# LCD_Connectors.net
KiCad netlist of a schematic drawn in Altium Designer
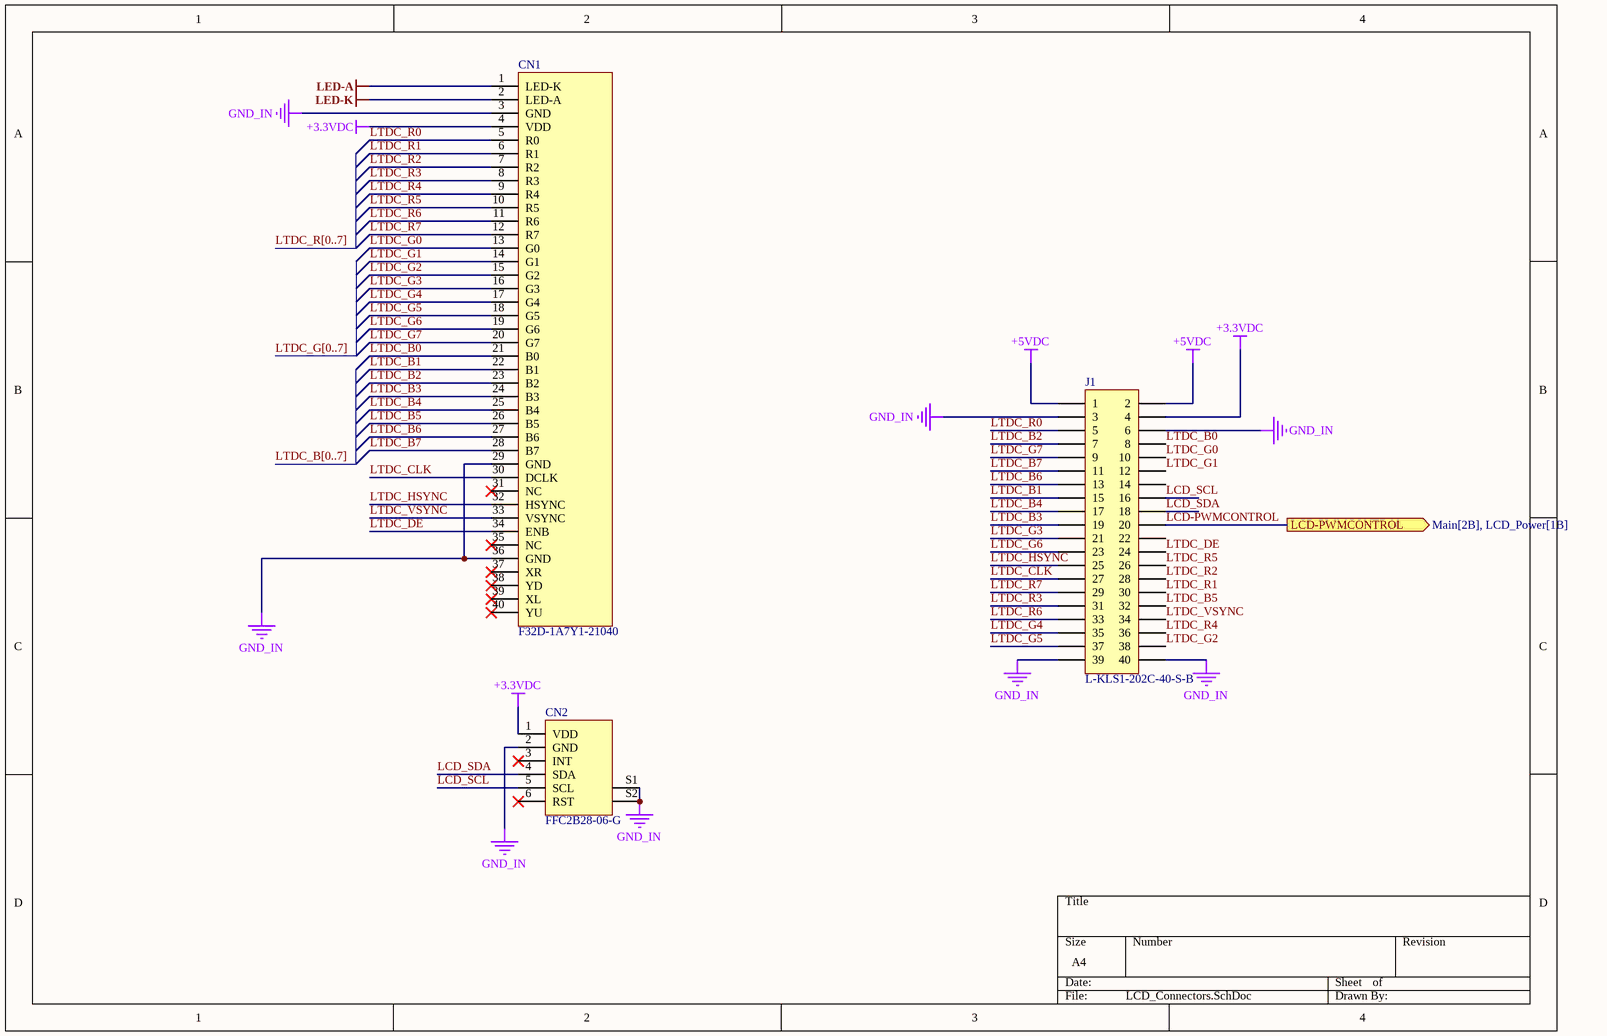
[diagram p0: LCD_Connectors.SchDoc]

(export (version "E")
  (design (tool "Eeschema 10.0.6"))
  (components
    (comp (ref "CN1")
      (value "F32D-1A7Y1-21040")
      (footprint "FPC_40POS_DOUBLESIDE")
      (description "CONN FFC BOTTOM 40POS 0.5MM R/A")
      (libsource (lib "IM_v1.0") (part "FPC CONN 40POS"))
    )
    (comp (ref "CN2")
      (value "FFC2B28-06-G")
      (footprint "FPC_6POS_DOUBLESIDE")
      (libsource (lib "IM_v1.0") (part "FPC CONN 6POS"))
    )
    (comp (ref "J1")
      (value "L-KLS1-202C-40-S-B")
      (footprint "L-KLS1-202C-40-T-B")
      (description "BOX HEADER 40PIN(2x20) 1.27MM THT V/T MALE BLACK")
      (libsource (lib "IM_v1.0") (part "2X20"))
    )
  )
  (nets
    (net (code "1") (name "+3.3VDC") (class "Default")
      (node (ref "CN1") (pin "4") (pinfunction "VDD_4") (pintype "passive"))
      (node (ref "CN2") (pin "1") (pinfunction "VDD_1") (pintype "passive"))
      (node (ref "J1") (pin "4") (pinfunction "4_4") (pintype "passive"))
    )
    (net (code "2") (name "+5VDC") (class "Default")
      (node (ref "J1") (pin "1") (pinfunction "1_1") (pintype "passive"))
      (node (ref "J1") (pin "2") (pinfunction "2_2") (pintype "passive"))
    )
    (net (code "3") (name "/LCD-PWMCONTROL") (class "Default")
      (node (ref "J1") (pin "20") (pinfunction "20_20") (pintype "passive"))
    )
    (net (code "4") (name "/LCD_SCL") (class "Default")
      (node (ref "CN2") (pin "5") (pinfunction "SCL_5") (pintype "passive"))
      (node (ref "J1") (pin "16") (pinfunction "16_16") (pintype "passive"))
    )
    (net (code "5") (name "/LCD_SDA") (class "Default")
      (node (ref "CN2") (pin "4") (pinfunction "SDA_4") (pintype "passive"))
      (node (ref "J1") (pin "18") (pinfunction "18_18") (pintype "passive"))
    )
    (net (code "6") (name "/LTDC_B0") (class "Default")
      (node (ref "CN1") (pin "21") (pinfunction "B0_21") (pintype "passive"))
      (node (ref "J1") (pin "8") (pinfunction "8_8") (pintype "passive"))
    )
    (net (code "7") (name "/LTDC_B1") (class "Default")
      (node (ref "CN1") (pin "22") (pinfunction "B1_22") (pintype "passive"))
      (node (ref "J1") (pin "15") (pinfunction "15_15") (pintype "passive"))
    )
    (net (code "8") (name "/LTDC_B2") (class "Default")
      (node (ref "CN1") (pin "23") (pinfunction "B2_23") (pintype "passive"))
      (node (ref "J1") (pin "7") (pinfunction "7_7") (pintype "passive"))
    )
    (net (code "9") (name "/LTDC_B3") (class "Default")
      (node (ref "CN1") (pin "24") (pinfunction "B3_24") (pintype "passive"))
      (node (ref "J1") (pin "19") (pinfunction "19_19") (pintype "passive"))
    )
    (net (code "10") (name "/LTDC_B4") (class "Default")
      (node (ref "CN1") (pin "25") (pinfunction "B4_25") (pintype "passive"))
      (node (ref "J1") (pin "17") (pinfunction "17_17") (pintype "passive"))
    )
    (net (code "11") (name "/LTDC_B5") (class "Default")
      (node (ref "CN1") (pin "26") (pinfunction "B5_26") (pintype "passive"))
      (node (ref "J1") (pin "32") (pinfunction "32_32") (pintype "passive"))
    )
    (net (code "12") (name "/LTDC_B6") (class "Default")
      (node (ref "CN1") (pin "27") (pinfunction "B6_27") (pintype "passive"))
      (node (ref "J1") (pin "13") (pinfunction "13_13") (pintype "passive"))
    )
    (net (code "13") (name "/LTDC_B7") (class "Default")
      (node (ref "CN1") (pin "28") (pinfunction "B7_28") (pintype "passive"))
      (node (ref "J1") (pin "11") (pinfunction "11_11") (pintype "passive"))
    )
    (net (code "15") (name "/LTDC_CLK") (class "Default")
      (node (ref "CN1") (pin "30") (pinfunction "DCLK_30") (pintype "passive"))
      (node (ref "J1") (pin "27") (pinfunction "27_27") (pintype "passive"))
    )
    (net (code "16") (name "/LTDC_DE") (class "Default")
      (node (ref "CN1") (pin "34") (pinfunction "ENB_34") (pintype "passive"))
      (node (ref "J1") (pin "24") (pinfunction "24_24") (pintype "passive"))
    )
    (net (code "17") (name "/LTDC_G0") (class "Default")
      (node (ref "CN1") (pin "13") (pinfunction "G0_13") (pintype "passive"))
      (node (ref "J1") (pin "10") (pinfunction "10_10") (pintype "passive"))
    )
    (net (code "18") (name "/LTDC_G1") (class "Default")
      (node (ref "CN1") (pin "14") (pinfunction "G1_14") (pintype "passive"))
      (node (ref "J1") (pin "12") (pinfunction "12_12") (pintype "passive"))
    )
    (net (code "19") (name "/LTDC_G2") (class "Default")
      (node (ref "CN1") (pin "15") (pinfunction "G2_15") (pintype "passive"))
      (node (ref "J1") (pin "38") (pinfunction "38_38") (pintype "passive"))
    )
    (net (code "20") (name "/LTDC_G3") (class "Default")
      (node (ref "CN1") (pin "16") (pinfunction "G3_16") (pintype "passive"))
      (node (ref "J1") (pin "21") (pinfunction "21_21") (pintype "passive"))
    )
    (net (code "21") (name "/LTDC_G4") (class "Default")
      (node (ref "CN1") (pin "17") (pinfunction "G4_17") (pintype "passive"))
      (node (ref "J1") (pin "35") (pinfunction "35_35") (pintype "passive"))
    )
    (net (code "22") (name "/LTDC_G5") (class "Default")
      (node (ref "CN1") (pin "18") (pinfunction "G5_18") (pintype "passive"))
      (node (ref "J1") (pin "37") (pinfunction "37_37") (pintype "passive"))
    )
    (net (code "23") (name "/LTDC_G6") (class "Default")
      (node (ref "CN1") (pin "19") (pinfunction "G6_19") (pintype "passive"))
      (node (ref "J1") (pin "23") (pinfunction "23_23") (pintype "passive"))
    )
    (net (code "24") (name "/LTDC_G7") (class "Default")
      (node (ref "CN1") (pin "20") (pinfunction "G7_20") (pintype "passive"))
      (node (ref "J1") (pin "9") (pinfunction "9_9") (pintype "passive"))
    )
    (net (code "26") (name "/LTDC_HSYNC") (class "Default")
      (node (ref "CN1") (pin "32") (pinfunction "HSYNC_32") (pintype "passive"))
      (node (ref "J1") (pin "25") (pinfunction "25_25") (pintype "passive"))
    )
    (net (code "27") (name "/LTDC_R0") (class "Default")
      (node (ref "CN1") (pin "5") (pinfunction "R0_5") (pintype "passive"))
      (node (ref "J1") (pin "5") (pinfunction "5_5") (pintype "passive"))
    )
    (net (code "28") (name "/LTDC_R1") (class "Default")
      (node (ref "CN1") (pin "6") (pinfunction "R1_6") (pintype "passive"))
      (node (ref "J1") (pin "30") (pinfunction "30_30") (pintype "passive"))
    )
    (net (code "29") (name "/LTDC_R2") (class "Default")
      (node (ref "CN1") (pin "7") (pinfunction "R2_7") (pintype "passive"))
      (node (ref "J1") (pin "28") (pinfunction "28_28") (pintype "passive"))
    )
    (net (code "30") (name "/LTDC_R3") (class "Default")
      (node (ref "CN1") (pin "8") (pinfunction "R3_8") (pintype "passive"))
      (node (ref "J1") (pin "31") (pinfunction "31_31") (pintype "passive"))
    )
    (net (code "31") (name "/LTDC_R4") (class "Default")
      (node (ref "CN1") (pin "9") (pinfunction "R4_9") (pintype "passive"))
      (node (ref "J1") (pin "36") (pinfunction "36_36") (pintype "passive"))
    )
    (net (code "32") (name "/LTDC_R5") (class "Default")
      (node (ref "CN1") (pin "10") (pinfunction "R5_10") (pintype "passive"))
      (node (ref "J1") (pin "26") (pinfunction "26_26") (pintype "passive"))
    )
    (net (code "33") (name "/LTDC_R6") (class "Default")
      (node (ref "CN1") (pin "11") (pinfunction "R6_11") (pintype "passive"))
      (node (ref "J1") (pin "33") (pinfunction "33_33") (pintype "passive"))
    )
    (net (code "34") (name "/LTDC_R7") (class "Default")
      (node (ref "CN1") (pin "12") (pinfunction "R7_12") (pintype "passive"))
      (node (ref "J1") (pin "29") (pinfunction "29_29") (pintype "passive"))
    )
    (net (code "36") (name "/LTDC_VSYNC") (class "Default")
      (node (ref "CN1") (pin "33") (pinfunction "VSYNC_33") (pintype "passive"))
      (node (ref "J1") (pin "34") (pinfunction "34_34") (pintype "passive"))
    )
    (net (code "37") (name "GND_IN") (class "Default")
      (node (ref "CN1") (pin "29") (pinfunction "GND_29") (pintype "passive"))
      (node (ref "CN1") (pin "3") (pinfunction "GND_3") (pintype "passive"))
      (node (ref "CN1") (pin "36") (pinfunction "GND_36") (pintype "passive"))
      (node (ref "CN2") (pin "2") (pinfunction "GND_2") (pintype "passive"))
      (node (ref "CN2") (pin "S1") (pinfunction "SHIELD_S1") (pintype "passive"))
      (node (ref "CN2") (pin "S2") (pinfunction "SHIELD_S2") (pintype "passive"))
      (node (ref "J1") (pin "3") (pinfunction "3_3") (pintype "passive"))
      (node (ref "J1") (pin "39") (pinfunction "39_39") (pintype "passive"))
      (node (ref "J1") (pin "40") (pinfunction "40_40") (pintype "passive"))
      (node (ref "J1") (pin "6") (pinfunction "6_6") (pintype "passive"))
    )
    (net (code "38") (name "LED-A") (class "Default")
      (node (ref "CN1") (pin "1") (pinfunction "LED-K_1") (pintype "passive"))
    )
    (net (code "39") (name "LED-K") (class "Default")
      (node (ref "CN1") (pin "2") (pinfunction "LED-A_2") (pintype "passive"))
    )
    (net (code "40") (name "unconnected-(CN1-NC-Pad31)") (class "Default")
      (node (ref "CN1") (pin "31") (pinfunction "NC_31") (pintype "passive+no_connect"))
    )
    (net (code "41") (name "unconnected-(CN1-NC-Pad35)") (class "Default")
      (node (ref "CN1") (pin "35") (pinfunction "NC_35") (pintype "passive+no_connect"))
    )
    (net (code "42") (name "unconnected-(CN1-XL-Pad39)") (class "Default")
      (node (ref "CN1") (pin "39") (pinfunction "XL_39") (pintype "passive+no_connect"))
    )
    (net (code "43") (name "unconnected-(CN1-XR-Pad37)") (class "Default")
      (node (ref "CN1") (pin "37") (pinfunction "XR_37") (pintype "passive+no_connect"))
    )
    (net (code "44") (name "unconnected-(CN1-YD-Pad38)") (class "Default")
      (node (ref "CN1") (pin "38") (pinfunction "YD_38") (pintype "passive+no_connect"))
    )
    (net (code "45") (name "unconnected-(CN1-YU-Pad40)") (class "Default")
      (node (ref "CN1") (pin "40") (pinfunction "YU_40") (pintype "passive+no_connect"))
    )
    (net (code "46") (name "unconnected-(CN2-INT-Pad3)") (class "Default")
      (node (ref "CN2") (pin "3") (pinfunction "INT_3") (pintype "passive+no_connect"))
    )
    (net (code "47") (name "unconnected-(CN2-RST-Pad6)") (class "Default")
      (node (ref "CN2") (pin "6") (pinfunction "RST_6") (pintype "passive+no_connect"))
    )
    (net (code "48") (name "unconnected-(J1-Pad14)") (class "Default")
      (node (ref "J1") (pin "14") (pinfunction "14_14") (pintype "passive"))
    )
    (net (code "49") (name "unconnected-(J1-Pad22)") (class "Default")
      (node (ref "J1") (pin "22") (pinfunction "22_22") (pintype "passive"))
    )
  )
)
